# Title.net
KiCad netlist of a schematic drawn in Altium Designer
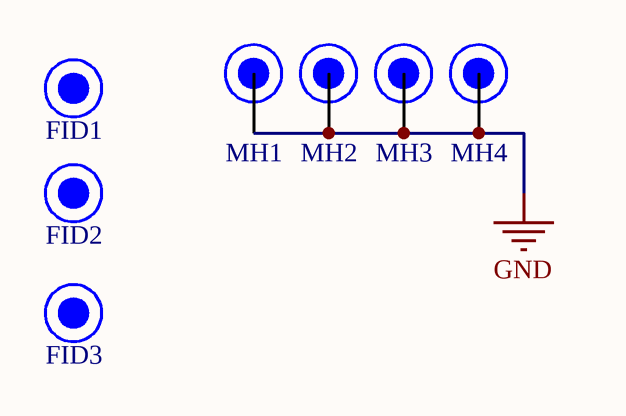
[diagram p0: Title.SchDoc]

(export (version "E")
  (design (tool "Eeschema 10.0.6"))
  (components
    (comp (ref "FID1")
      (value "Fiducial 1mm")
      (footprint "FID_1MM")
      (description "FID - 1MM")
      (libsource (lib "SecureBot") (part "FID - 1MM"))
    )
    (comp (ref "FID2")
      (value "Fiducial 1mm")
      (footprint "FID_1MM")
      (description "FID - 1MM")
      (libsource (lib "SecureBot") (part "FID - 1MM"))
    )
    (comp (ref "FID3")
      (value "Fiducial 1mm")
      (footprint "FID_1MM")
      (description "FID - 1MM")
      (libsource (lib "SecureBot") (part "FID - 1MM"))
    )
    (comp (ref "MH1")
      (value "Mounting Hole 6/32")
      (footprint "MH_ENG_6-32")
      (libsource (lib "SecureBot") (part "MH - 6-32"))
    )
    (comp (ref "MH2")
      (value "Mounting Hole 6/32")
      (footprint "MH_ENG_6-32")
      (libsource (lib "SecureBot") (part "MH - 6-32"))
    )
    (comp (ref "MH3")
      (value "Mounting Hole 6/32")
      (footprint "MH_ENG_6-32")
      (libsource (lib "SecureBot") (part "MH - 6-32"))
    )
    (comp (ref "MH4")
      (value "Mounting Hole 6/32")
      (footprint "MH_ENG_6-32")
      (libsource (lib "SecureBot") (part "MH - 6-32"))
    )
  )
  (nets
    (net (code "1") (name "GND") (class "Default")
      (node (ref "MH1") (pin "1") (pinfunction "1_1") (pintype "passive"))
      (node (ref "MH2") (pin "1") (pinfunction "1_1") (pintype "passive"))
      (node (ref "MH3") (pin "1") (pinfunction "1_1") (pintype "passive"))
      (node (ref "MH4") (pin "1") (pinfunction "1_1") (pintype "passive"))
    )
  )
)
